# d150_in8.net
KiCad netlist of a schematic drawn in EAGLE
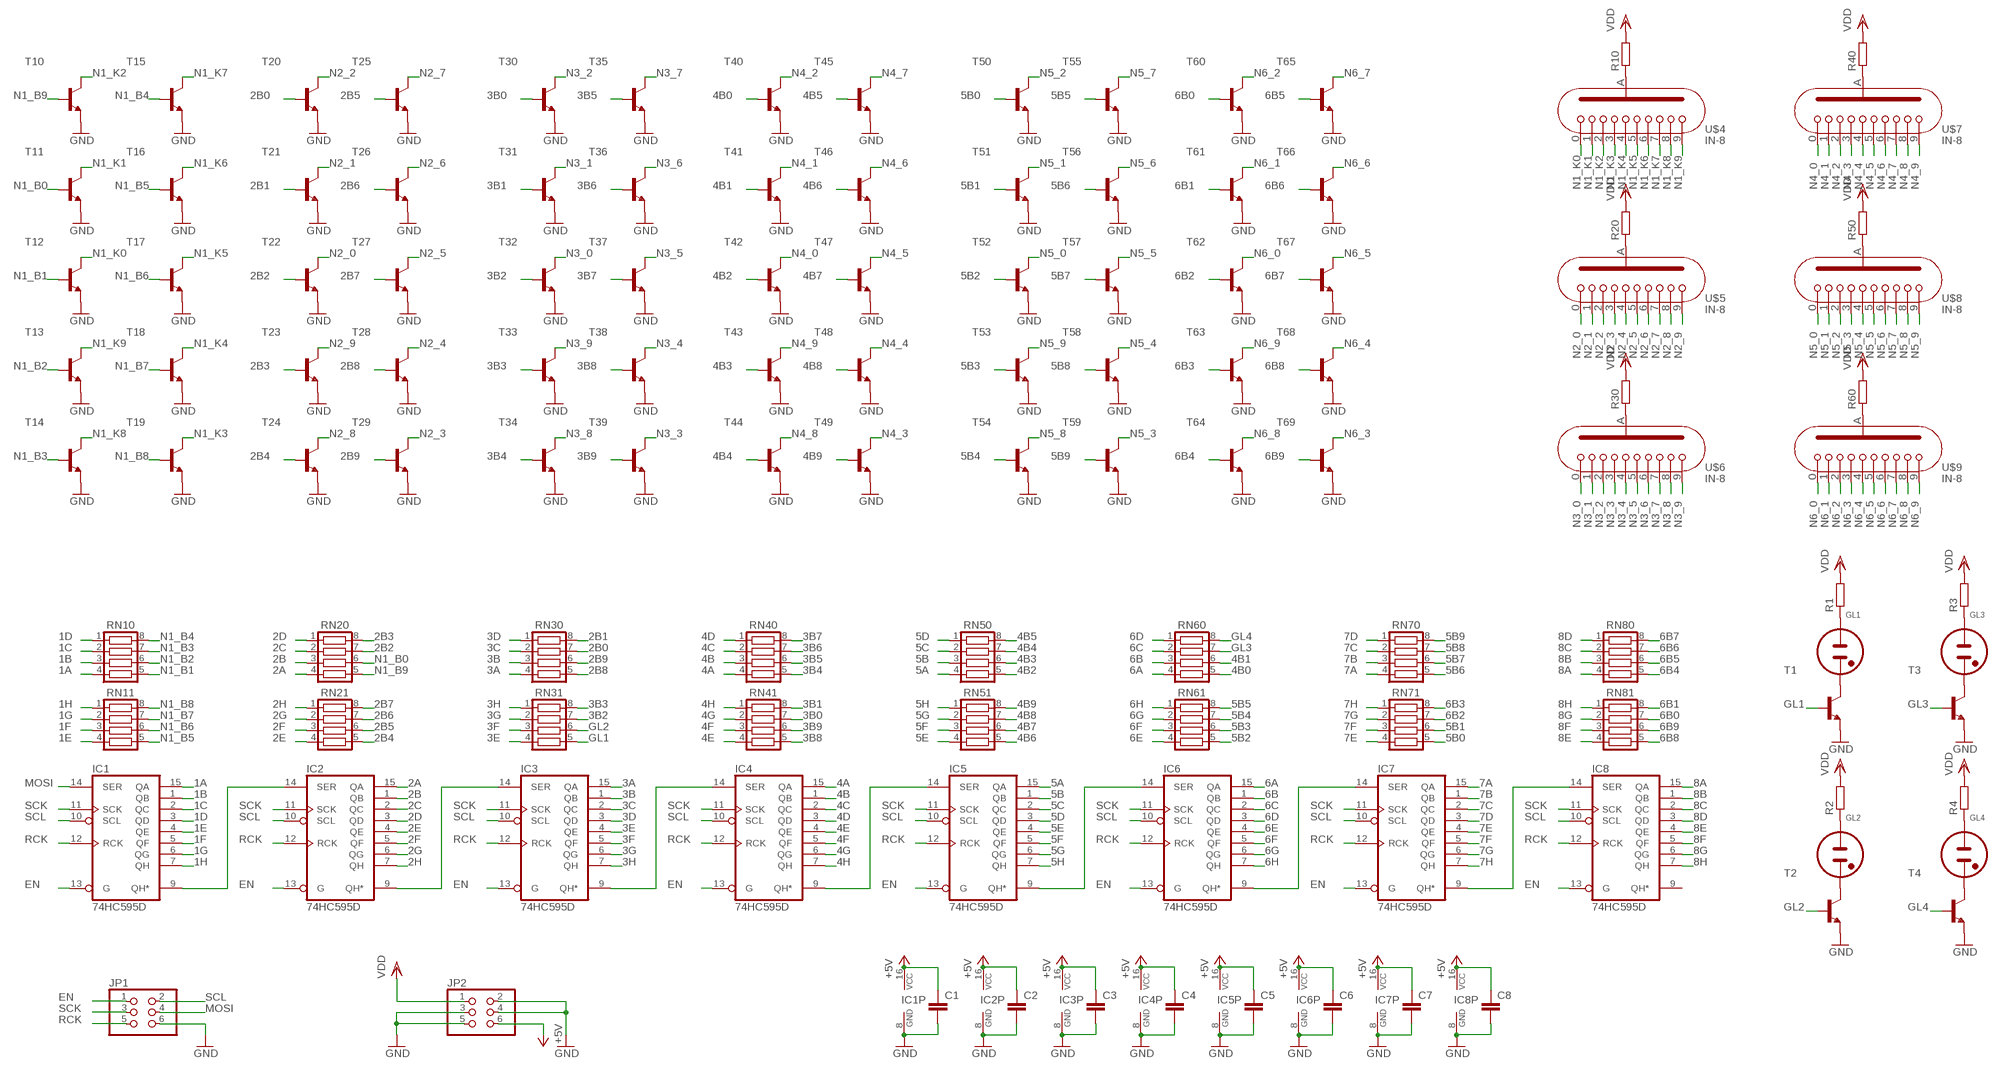
[diagram p0: schematic, sheet 1]

(export (version "E")
  (design (tool "Eeschema 10.0.6"))
  (components
    (comp (ref "C1")
      (value "C-EUC0603")
      (footprint "eagle-import:C0603")
      (libsource (lib "eagle-import") (part "C-EUC0603"))
    )
    (comp (ref "C2")
      (value "C-EUC0603")
      (footprint "eagle-import:C0603")
      (libsource (lib "eagle-import") (part "C-EUC0603"))
    )
    (comp (ref "C3")
      (value "C-EUC0603")
      (footprint "eagle-import:C0603")
      (libsource (lib "eagle-import") (part "C-EUC0603"))
    )
    (comp (ref "C4")
      (value "C-EUC0603")
      (footprint "eagle-import:C0603")
      (libsource (lib "eagle-import") (part "C-EUC0603"))
    )
    (comp (ref "C5")
      (value "C-EUC0603")
      (footprint "eagle-import:C0603")
      (libsource (lib "eagle-import") (part "C-EUC0603"))
    )
    (comp (ref "C6")
      (value "C-EUC0603")
      (footprint "eagle-import:C0603")
      (libsource (lib "eagle-import") (part "C-EUC0603"))
    )
    (comp (ref "C7")
      (value "C-EUC0603")
      (footprint "eagle-import:C0603")
      (libsource (lib "eagle-import") (part "C-EUC0603"))
    )
    (comp (ref "C8")
      (value "C-EUC0603")
      (footprint "eagle-import:C0603")
      (libsource (lib "eagle-import") (part "C-EUC0603"))
    )
    (comp (ref "GL1")
      (value "NE2-NEON-BULB-DRILL")
      (footprint "eagle-import:NE2-NEON-BULB-DRILL")
      (libsource (lib "eagle-import") (part "NE2-NEON-BULB-DRILL"))
    )
    (comp (ref "GL2")
      (value "NE2-NEON-BULB-DRILL")
      (footprint "eagle-import:NE2-NEON-BULB-DRILL")
      (libsource (lib "eagle-import") (part "NE2-NEON-BULB-DRILL"))
    )
    (comp (ref "GL3")
      (value "NE2-NEON-BULB-DRILL")
      (footprint "eagle-import:NE2-NEON-BULB-DRILL")
      (libsource (lib "eagle-import") (part "NE2-NEON-BULB-DRILL"))
    )
    (comp (ref "GL4")
      (value "NE2-NEON-BULB-DRILL")
      (footprint "eagle-import:NE2-NEON-BULB-DRILL")
      (libsource (lib "eagle-import") (part "NE2-NEON-BULB-DRILL"))
    )
    (comp (ref "IC1")
      (value "74HC595D")
      (footprint "eagle-import:SO16")
      (libsource (lib "eagle-import") (part "74595DHC"))
    )
    (comp (ref "IC2")
      (value "74HC595D")
      (footprint "eagle-import:SO16")
      (libsource (lib "eagle-import") (part "74595DHC"))
    )
    (comp (ref "IC3")
      (value "74HC595D")
      (footprint "eagle-import:SO16")
      (libsource (lib "eagle-import") (part "74595DHC"))
    )
    (comp (ref "IC4")
      (value "74HC595D")
      (footprint "eagle-import:SO16")
      (libsource (lib "eagle-import") (part "74595DHC"))
    )
    (comp (ref "IC5")
      (value "74HC595D")
      (footprint "eagle-import:SO16")
      (libsource (lib "eagle-import") (part "74595DHC"))
    )
    (comp (ref "IC6")
      (value "74HC595D")
      (footprint "eagle-import:SO16")
      (libsource (lib "eagle-import") (part "74595DHC"))
    )
    (comp (ref "IC7")
      (value "74HC595D")
      (footprint "eagle-import:SO16")
      (libsource (lib "eagle-import") (part "74595DHC"))
    )
    (comp (ref "IC8")
      (value "74HC595D")
      (footprint "eagle-import:SO16")
      (libsource (lib "eagle-import") (part "74595DHC"))
    )
    (comp (ref "JP1")
      (value "PINHD-2X3_2.54-SMD")
      (footprint "eagle-import:2X03SMD")
      (libsource (lib "eagle-import") (part "PINHD-2X3_2.54-SMD"))
    )
    (comp (ref "JP2")
      (value "PINHD-2X3_2.54-SMD")
      (footprint "eagle-import:2X03SMD")
      (libsource (lib "eagle-import") (part "PINHD-2X3_2.54-SMD"))
    )
    (comp (ref "R1")
      (value "R-EU_R0603")
      (footprint "eagle-import:R0603")
      (libsource (lib "eagle-import") (part "R-EU_R0603"))
    )
    (comp (ref "R2")
      (value "R-EU_R0603")
      (footprint "eagle-import:R0603")
      (libsource (lib "eagle-import") (part "R-EU_R0603"))
    )
    (comp (ref "R3")
      (value "R-EU_R0603")
      (footprint "eagle-import:R0603")
      (libsource (lib "eagle-import") (part "R-EU_R0603"))
    )
    (comp (ref "R4")
      (value "R-EU_R0603")
      (footprint "eagle-import:R0603")
      (libsource (lib "eagle-import") (part "R-EU_R0603"))
    )
    (comp (ref "R10")
      (value "R-EU_R0603")
      (footprint "eagle-import:R0603")
      (libsource (lib "eagle-import") (part "R-EU_R0603"))
    )
    (comp (ref "R20")
      (value "R-EU_R0603")
      (footprint "eagle-import:R0603")
      (libsource (lib "eagle-import") (part "R-EU_R0603"))
    )
    (comp (ref "R30")
      (value "R-EU_R0603")
      (footprint "eagle-import:R0603")
      (libsource (lib "eagle-import") (part "R-EU_R0603"))
    )
    (comp (ref "R40")
      (value "R-EU_R0603")
      (footprint "eagle-import:R0603")
      (libsource (lib "eagle-import") (part "R-EU_R0603"))
    )
    (comp (ref "R50")
      (value "R-EU_R0603")
      (footprint "eagle-import:R0603")
      (libsource (lib "eagle-import") (part "R-EU_R0603"))
    )
    (comp (ref "R60")
      (value "R-EU_R0603")
      (footprint "eagle-import:R0603")
      (libsource (lib "eagle-import") (part "R-EU_R0603"))
    )
    (comp (ref "RN10")
      (value "CTS742C083")
      (footprint "eagle-import:CTS742C083")
      (fields (field (name "OC_FARNELL") "unknown") (field (name "OC_NEWARK") "unknown"))
      (libsource (lib "eagle-import") (part "CTS742C083"))
    )
    (comp (ref "RN11")
      (value "CTS742C083")
      (footprint "eagle-import:CTS742C083")
      (fields (field (name "OC_FARNELL") "unknown") (field (name "OC_NEWARK") "unknown"))
      (libsource (lib "eagle-import") (part "CTS742C083"))
    )
    (comp (ref "RN20")
      (value "CTS742C083")
      (footprint "eagle-import:CTS742C083")
      (fields (field (name "OC_FARNELL") "unknown") (field (name "OC_NEWARK") "unknown"))
      (libsource (lib "eagle-import") (part "CTS742C083"))
    )
    (comp (ref "RN21")
      (value "CTS742C083")
      (footprint "eagle-import:CTS742C083")
      (fields (field (name "OC_FARNELL") "unknown") (field (name "OC_NEWARK") "unknown"))
      (libsource (lib "eagle-import") (part "CTS742C083"))
    )
    (comp (ref "RN30")
      (value "CTS742C083")
      (footprint "eagle-import:CTS742C083")
      (fields (field (name "OC_FARNELL") "unknown") (field (name "OC_NEWARK") "unknown"))
      (libsource (lib "eagle-import") (part "CTS742C083"))
    )
    (comp (ref "RN31")
      (value "CTS742C083")
      (footprint "eagle-import:CTS742C083")
      (fields (field (name "OC_FARNELL") "unknown") (field (name "OC_NEWARK") "unknown"))
      (libsource (lib "eagle-import") (part "CTS742C083"))
    )
    (comp (ref "RN40")
      (value "CTS742C083")
      (footprint "eagle-import:CTS742C083")
      (fields (field (name "OC_FARNELL") "unknown") (field (name "OC_NEWARK") "unknown"))
      (libsource (lib "eagle-import") (part "CTS742C083"))
    )
    (comp (ref "RN41")
      (value "CTS742C083")
      (footprint "eagle-import:CTS742C083")
      (fields (field (name "OC_FARNELL") "unknown") (field (name "OC_NEWARK") "unknown"))
      (libsource (lib "eagle-import") (part "CTS742C083"))
    )
    (comp (ref "RN50")
      (value "CTS742C083")
      (footprint "eagle-import:CTS742C083")
      (fields (field (name "OC_FARNELL") "unknown") (field (name "OC_NEWARK") "unknown"))
      (libsource (lib "eagle-import") (part "CTS742C083"))
    )
    (comp (ref "RN51")
      (value "CTS742C083")
      (footprint "eagle-import:CTS742C083")
      (fields (field (name "OC_FARNELL") "unknown") (field (name "OC_NEWARK") "unknown"))
      (libsource (lib "eagle-import") (part "CTS742C083"))
    )
    (comp (ref "RN60")
      (value "CTS742C083")
      (footprint "eagle-import:CTS742C083")
      (fields (field (name "OC_FARNELL") "unknown") (field (name "OC_NEWARK") "unknown"))
      (libsource (lib "eagle-import") (part "CTS742C083"))
    )
    (comp (ref "RN61")
      (value "CTS742C083")
      (footprint "eagle-import:CTS742C083")
      (fields (field (name "OC_FARNELL") "unknown") (field (name "OC_NEWARK") "unknown"))
      (libsource (lib "eagle-import") (part "CTS742C083"))
    )
    (comp (ref "RN70")
      (value "CTS742C083")
      (footprint "eagle-import:CTS742C083")
      (fields (field (name "OC_FARNELL") "unknown") (field (name "OC_NEWARK") "unknown"))
      (libsource (lib "eagle-import") (part "CTS742C083"))
    )
    (comp (ref "RN71")
      (value "CTS742C083")
      (footprint "eagle-import:CTS742C083")
      (fields (field (name "OC_FARNELL") "unknown") (field (name "OC_NEWARK") "unknown"))
      (libsource (lib "eagle-import") (part "CTS742C083"))
    )
    (comp (ref "RN80")
      (value "CTS742C083")
      (footprint "eagle-import:CTS742C083")
      (fields (field (name "OC_FARNELL") "unknown") (field (name "OC_NEWARK") "unknown"))
      (libsource (lib "eagle-import") (part "CTS742C083"))
    )
    (comp (ref "RN81")
      (value "CTS742C083")
      (footprint "eagle-import:CTS742C083")
      (fields (field (name "OC_FARNELL") "unknown") (field (name "OC_NEWARK") "unknown"))
      (libsource (lib "eagle-import") (part "CTS742C083"))
    )
    (comp (ref "T1")
      (value "SMBTA42")
      (footprint "eagle-import:SOT23")
      (libsource (lib "eagle-import") (part "SMBTA42"))
    )
    (comp (ref "T2")
      (value "SMBTA42")
      (footprint "eagle-import:SOT23")
      (libsource (lib "eagle-import") (part "SMBTA42"))
    )
    (comp (ref "T3")
      (value "SMBTA42")
      (footprint "eagle-import:SOT23")
      (libsource (lib "eagle-import") (part "SMBTA42"))
    )
    (comp (ref "T4")
      (value "SMBTA42")
      (footprint "eagle-import:SOT23")
      (libsource (lib "eagle-import") (part "SMBTA42"))
    )
    (comp (ref "T10")
      (value "SMBTA42")
      (footprint "eagle-import:SOT23")
      (libsource (lib "eagle-import") (part "SMBTA42"))
    )
    (comp (ref "T11")
      (value "SMBTA42")
      (footprint "eagle-import:SOT23")
      (libsource (lib "eagle-import") (part "SMBTA42"))
    )
    (comp (ref "T12")
      (value "SMBTA42")
      (footprint "eagle-import:SOT23")
      (libsource (lib "eagle-import") (part "SMBTA42"))
    )
    (comp (ref "T13")
      (value "SMBTA42")
      (footprint "eagle-import:SOT23")
      (libsource (lib "eagle-import") (part "SMBTA42"))
    )
    (comp (ref "T14")
      (value "SMBTA42")
      (footprint "eagle-import:SOT23")
      (libsource (lib "eagle-import") (part "SMBTA42"))
    )
    (comp (ref "T15")
      (value "SMBTA42")
      (footprint "eagle-import:SOT23")
      (libsource (lib "eagle-import") (part "SMBTA42"))
    )
    (comp (ref "T16")
      (value "SMBTA42")
      (footprint "eagle-import:SOT23")
      (libsource (lib "eagle-import") (part "SMBTA42"))
    )
    (comp (ref "T17")
      (value "SMBTA42")
      (footprint "eagle-import:SOT23")
      (libsource (lib "eagle-import") (part "SMBTA42"))
    )
    (comp (ref "T18")
      (value "SMBTA42")
      (footprint "eagle-import:SOT23")
      (libsource (lib "eagle-import") (part "SMBTA42"))
    )
    (comp (ref "T19")
      (value "SMBTA42")
      (footprint "eagle-import:SOT23")
      (libsource (lib "eagle-import") (part "SMBTA42"))
    )
    (comp (ref "T20")
      (value "SMBTA42")
      (footprint "eagle-import:SOT23")
      (libsource (lib "eagle-import") (part "SMBTA42"))
    )
    (comp (ref "T21")
      (value "SMBTA42")
      (footprint "eagle-import:SOT23")
      (libsource (lib "eagle-import") (part "SMBTA42"))
    )
    (comp (ref "T22")
      (value "SMBTA42")
      (footprint "eagle-import:SOT23")
      (libsource (lib "eagle-import") (part "SMBTA42"))
    )
    (comp (ref "T23")
      (value "SMBTA42")
      (footprint "eagle-import:SOT23")
      (libsource (lib "eagle-import") (part "SMBTA42"))
    )
    (comp (ref "T24")
      (value "SMBTA42")
      (footprint "eagle-import:SOT23")
      (libsource (lib "eagle-import") (part "SMBTA42"))
    )
    (comp (ref "T25")
      (value "SMBTA42")
      (footprint "eagle-import:SOT23")
      (libsource (lib "eagle-import") (part "SMBTA42"))
    )
    (comp (ref "T26")
      (value "SMBTA42")
      (footprint "eagle-import:SOT23")
      (libsource (lib "eagle-import") (part "SMBTA42"))
    )
    (comp (ref "T27")
      (value "SMBTA42")
      (footprint "eagle-import:SOT23")
      (libsource (lib "eagle-import") (part "SMBTA42"))
    )
    (comp (ref "T28")
      (value "SMBTA42")
      (footprint "eagle-import:SOT23")
      (libsource (lib "eagle-import") (part "SMBTA42"))
    )
    (comp (ref "T29")
      (value "SMBTA42")
      (footprint "eagle-import:SOT23")
      (libsource (lib "eagle-import") (part "SMBTA42"))
    )
    (comp (ref "T30")
      (value "SMBTA42")
      (footprint "eagle-import:SOT23")
      (libsource (lib "eagle-import") (part "SMBTA42"))
    )
    (comp (ref "T31")
      (value "SMBTA42")
      (footprint "eagle-import:SOT23")
      (libsource (lib "eagle-import") (part "SMBTA42"))
    )
    (comp (ref "T32")
      (value "SMBTA42")
      (footprint "eagle-import:SOT23")
      (libsource (lib "eagle-import") (part "SMBTA42"))
    )
    (comp (ref "T33")
      (value "SMBTA42")
      (footprint "eagle-import:SOT23")
      (libsource (lib "eagle-import") (part "SMBTA42"))
    )
    (comp (ref "T34")
      (value "SMBTA42")
      (footprint "eagle-import:SOT23")
      (libsource (lib "eagle-import") (part "SMBTA42"))
    )
    (comp (ref "T35")
      (value "SMBTA42")
      (footprint "eagle-import:SOT23")
      (libsource (lib "eagle-import") (part "SMBTA42"))
    )
    (comp (ref "T36")
      (value "SMBTA42")
      (footprint "eagle-import:SOT23")
      (libsource (lib "eagle-import") (part "SMBTA42"))
    )
    (comp (ref "T37")
      (value "SMBTA42")
      (footprint "eagle-import:SOT23")
      (libsource (lib "eagle-import") (part "SMBTA42"))
    )
    (comp (ref "T38")
      (value "SMBTA42")
      (footprint "eagle-import:SOT23")
      (libsource (lib "eagle-import") (part "SMBTA42"))
    )
    (comp (ref "T39")
      (value "SMBTA42")
      (footprint "eagle-import:SOT23")
      (libsource (lib "eagle-import") (part "SMBTA42"))
    )
    (comp (ref "T40")
      (value "SMBTA42")
      (footprint "eagle-import:SOT23")
      (libsource (lib "eagle-import") (part "SMBTA42"))
    )
    (comp (ref "T41")
      (value "SMBTA42")
      (footprint "eagle-import:SOT23")
      (libsource (lib "eagle-import") (part "SMBTA42"))
    )
    (comp (ref "T42")
      (value "SMBTA42")
      (footprint "eagle-import:SOT23")
      (libsource (lib "eagle-import") (part "SMBTA42"))
    )
    (comp (ref "T43")
      (value "SMBTA42")
      (footprint "eagle-import:SOT23")
      (libsource (lib "eagle-import") (part "SMBTA42"))
    )
    (comp (ref "T44")
      (value "SMBTA42")
      (footprint "eagle-import:SOT23")
      (libsource (lib "eagle-import") (part "SMBTA42"))
    )
    (comp (ref "T45")
      (value "SMBTA42")
      (footprint "eagle-import:SOT23")
      (libsource (lib "eagle-import") (part "SMBTA42"))
    )
    (comp (ref "T46")
      (value "SMBTA42")
      (footprint "eagle-import:SOT23")
      (libsource (lib "eagle-import") (part "SMBTA42"))
    )
    (comp (ref "T47")
      (value "SMBTA42")
      (footprint "eagle-import:SOT23")
      (libsource (lib "eagle-import") (part "SMBTA42"))
    )
    (comp (ref "T48")
      (value "SMBTA42")
      (footprint "eagle-import:SOT23")
      (libsource (lib "eagle-import") (part "SMBTA42"))
    )
    (comp (ref "T49")
      (value "SMBTA42")
      (footprint "eagle-import:SOT23")
      (libsource (lib "eagle-import") (part "SMBTA42"))
    )
    (comp (ref "T50")
      (value "SMBTA42")
      (footprint "eagle-import:SOT23")
      (libsource (lib "eagle-import") (part "SMBTA42"))
    )
    (comp (ref "T51")
      (value "SMBTA42")
      (footprint "eagle-import:SOT23")
      (libsource (lib "eagle-import") (part "SMBTA42"))
    )
    (comp (ref "T52")
      (value "SMBTA42")
      (footprint "eagle-import:SOT23")
      (libsource (lib "eagle-import") (part "SMBTA42"))
    )
    (comp (ref "T53")
      (value "SMBTA42")
      (footprint "eagle-import:SOT23")
      (libsource (lib "eagle-import") (part "SMBTA42"))
    )
    (comp (ref "T54")
      (value "SMBTA42")
      (footprint "eagle-import:SOT23")
      (libsource (lib "eagle-import") (part "SMBTA42"))
    )
    (comp (ref "T55")
      (value "SMBTA42")
      (footprint "eagle-import:SOT23")
      (libsource (lib "eagle-import") (part "SMBTA42"))
    )
    (comp (ref "T56")
      (value "SMBTA42")
      (footprint "eagle-import:SOT23")
      (libsource (lib "eagle-import") (part "SMBTA42"))
    )
    (comp (ref "T57")
      (value "SMBTA42")
      (footprint "eagle-import:SOT23")
      (libsource (lib "eagle-import") (part "SMBTA42"))
    )
    (comp (ref "T58")
      (value "SMBTA42")
      (footprint "eagle-import:SOT23")
      (libsource (lib "eagle-import") (part "SMBTA42"))
    )
    (comp (ref "T59")
      (value "SMBTA42")
      (footprint "eagle-import:SOT23")
      (libsource (lib "eagle-import") (part "SMBTA42"))
    )
    (comp (ref "T60")
      (value "SMBTA42")
      (footprint "eagle-import:SOT23")
      (libsource (lib "eagle-import") (part "SMBTA42"))
    )
    (comp (ref "T61")
      (value "SMBTA42")
      (footprint "eagle-import:SOT23")
      (libsource (lib "eagle-import") (part "SMBTA42"))
    )
    (comp (ref "T62")
      (value "SMBTA42")
      (footprint "eagle-import:SOT23")
      (libsource (lib "eagle-import") (part "SMBTA42"))
    )
    (comp (ref "T63")
      (value "SMBTA42")
      (footprint "eagle-import:SOT23")
      (libsource (lib "eagle-import") (part "SMBTA42"))
    )
    (comp (ref "T64")
      (value "SMBTA42")
      (footprint "eagle-import:SOT23")
      (libsource (lib "eagle-import") (part "SMBTA42"))
    )
    (comp (ref "T65")
      (value "SMBTA42")
      (footprint "eagle-import:SOT23")
      (libsource (lib "eagle-import") (part "SMBTA42"))
    )
    (comp (ref "T66")
      (value "SMBTA42")
      (footprint "eagle-import:SOT23")
      (libsource (lib "eagle-import") (part "SMBTA42"))
    )
    (comp (ref "T67")
      (value "SMBTA42")
      (footprint "eagle-import:SOT23")
      (libsource (lib "eagle-import") (part "SMBTA42"))
    )
    (comp (ref "T68")
      (value "SMBTA42")
      (footprint "eagle-import:SOT23")
      (libsource (lib "eagle-import") (part "SMBTA42"))
    )
    (comp (ref "T69")
      (value "SMBTA42")
      (footprint "eagle-import:SOT23")
      (libsource (lib "eagle-import") (part "SMBTA42"))
    )
    (comp (ref "U$4")
      (value "IN-8")
      (footprint "eagle-import:IN-8")
      (libsource (lib "eagle-import") (part "IN-8"))
    )
    (comp (ref "U$5")
      (value "IN-8")
      (footprint "eagle-import:IN-8")
      (libsource (lib "eagle-import") (part "IN-8"))
    )
    (comp (ref "U$6")
      (value "IN-8")
      (footprint "eagle-import:IN-8")
      (libsource (lib "eagle-import") (part "IN-8"))
    )
    (comp (ref "U$7")
      (value "IN-8")
      (footprint "eagle-import:IN-8")
      (libsource (lib "eagle-import") (part "IN-8"))
    )
    (comp (ref "U$8")
      (value "IN-8")
      (footprint "eagle-import:IN-8")
      (libsource (lib "eagle-import") (part "IN-8"))
    )
    (comp (ref "U$9")
      (value "IN-8")
      (footprint "eagle-import:IN-8")
      (libsource (lib "eagle-import") (part "IN-8"))
    )
  )
  (nets
    (net (code "1") (name "+5V") (class "Default")
      (node (ref "C1") (pin "1") (pinfunction "1_1") (pintype "passive"))
      (node (ref "C2") (pin "1") (pinfunction "1_1") (pintype "passive"))
      (node (ref "C3") (pin "1") (pinfunction "1_1") (pintype "passive"))
      (node (ref "C4") (pin "1") (pinfunction "1_1") (pintype "passive"))
      (node (ref "C5") (pin "1") (pinfunction "1_1") (pintype "passive"))
      (node (ref "C6") (pin "1") (pinfunction "1_1") (pintype "passive"))
      (node (ref "C7") (pin "1") (pinfunction "1_1") (pintype "passive"))
      (node (ref "C8") (pin "1") (pinfunction "1_1") (pintype "passive"))
      (node (ref "IC1") (pin "16") (pinfunction "VCC_16") (pintype "power_in"))
      (node (ref "IC2") (pin "16") (pinfunction "VCC_16") (pintype "power_in"))
      (node (ref "IC3") (pin "16") (pinfunction "VCC_16") (pintype "power_in"))
      (node (ref "IC4") (pin "16") (pinfunction "VCC_16") (pintype "power_in"))
      (node (ref "IC5") (pin "16") (pinfunction "VCC_16") (pintype "power_in"))
      (node (ref "IC6") (pin "16") (pinfunction "VCC_16") (pintype "power_in"))
      (node (ref "IC7") (pin "16") (pinfunction "VCC_16") (pintype "power_in"))
      (node (ref "IC8") (pin "16") (pinfunction "VCC_16") (pintype "power_in"))
      (node (ref "JP2") (pin "6") (pinfunction "6_6") (pintype "passive"))
    )
    (net (code "2") (name "/1A") (class "Default")
      (node (ref "IC1") (pin "15") (pinfunction "QA_15") (pintype "tri_state"))
      (node (ref "RN10") (pin "4") (pinfunction "4_4") (pintype "passive"))
    )
    (net (code "3") (name "/1B") (class "Default")
      (node (ref "IC1") (pin "1") (pinfunction "QB_1") (pintype "tri_state"))
      (node (ref "RN10") (pin "3") (pinfunction "3_3") (pintype "passive"))
    )
    (net (code "4") (name "/1C") (class "Default")
      (node (ref "IC1") (pin "2") (pinfunction "QC_2") (pintype "tri_state"))
      (node (ref "RN10") (pin "2") (pinfunction "2_2") (pintype "passive"))
    )
    (net (code "5") (name "/1D") (class "Default")
      (node (ref "IC1") (pin "3") (pinfunction "QD_3") (pintype "tri_state"))
      (node (ref "RN10") (pin "1") (pinfunction "1_1") (pintype "passive"))
    )
    (net (code "6") (name "/1E") (class "Default")
      (node (ref "IC1") (pin "4") (pinfunction "QE_4") (pintype "tri_state"))
      (node (ref "RN11") (pin "4") (pinfunction "4_4") (pintype "passive"))
    )
    (net (code "7") (name "/1F") (class "Default")
      (node (ref "IC1") (pin "5") (pinfunction "QF_5") (pintype "tri_state"))
      (node (ref "RN11") (pin "3") (pinfunction "3_3") (pintype "passive"))
    )
    (net (code "8") (name "/1G") (class "Default")
      (node (ref "IC1") (pin "6") (pinfunction "QG_6") (pintype "tri_state"))
      (node (ref "RN11") (pin "2") (pinfunction "2_2") (pintype "passive"))
    )
    (net (code "9") (name "/1H") (class "Default")
      (node (ref "IC1") (pin "7") (pinfunction "QH_7") (pintype "tri_state"))
      (node (ref "RN11") (pin "1") (pinfunction "1_1") (pintype "passive"))
    )
    (net (code "10") (name "/2A") (class "Default")
      (node (ref "IC2") (pin "15") (pinfunction "QA_15") (pintype "tri_state"))
      (node (ref "RN20") (pin "4") (pinfunction "4_4") (pintype "passive"))
    )
    (net (code "11") (name "/2B") (class "Default")
      (node (ref "IC2") (pin "1") (pinfunction "QB_1") (pintype "tri_state"))
      (node (ref "RN20") (pin "3") (pinfunction "3_3") (pintype "passive"))
    )
    (net (code "12") (name "/2B0") (class "Default")
      (node (ref "RN30") (pin "7") (pinfunction "7_7") (pintype "passive"))
      (node (ref "T20") (pin "1") (pinfunction "B_1") (pintype "passive"))
    )
    (net (code "13") (name "/2B1") (class "Default")
      (node (ref "RN30") (pin "8") (pinfunction "8_8") (pintype "passive"))
      (node (ref "T21") (pin "1") (pinfunction "B_1") (pintype "passive"))
    )
    (net (code "14") (name "/2B2") (class "Default")
      (node (ref "RN20") (pin "7") (pinfunction "7_7") (pintype "passive"))
      (node (ref "T22") (pin "1") (pinfunction "B_1") (pintype "passive"))
    )
    (net (code "15") (name "/2B3") (class "Default")
      (node (ref "RN20") (pin "8") (pinfunction "8_8") (pintype "passive"))
      (node (ref "T23") (pin "1") (pinfunction "B_1") (pintype "passive"))
    )
    (net (code "16") (name "/2B4") (class "Default")
      (node (ref "RN21") (pin "5") (pinfunction "5_5") (pintype "passive"))
      (node (ref "T24") (pin "1") (pinfunction "B_1") (pintype "passive"))
    )
    (net (code "17") (name "/2B5") (class "Default")
      (node (ref "RN21") (pin "6") (pinfunction "6_6") (pintype "passive"))
      (node (ref "T25") (pin "1") (pinfunction "B_1") (pintype "passive"))
    )
    (net (code "18") (name "/2B6") (class "Default")
      (node (ref "RN21") (pin "7") (pinfunction "7_7") (pintype "passive"))
      (node (ref "T26") (pin "1") (pinfunction "B_1") (pintype "passive"))
    )
    (net (code "19") (name "/2B7") (class "Default")
      (node (ref "RN21") (pin "8") (pinfunction "8_8") (pintype "passive"))
      (node (ref "T27") (pin "1") (pinfunction "B_1") (pintype "passive"))
    )
    (net (code "20") (name "/2B8") (class "Default")
      (node (ref "RN30") (pin "5") (pinfunction "5_5") (pintype "passive"))
      (node (ref "T28") (pin "1") (pinfunction "B_1") (pintype "passive"))
    )
    (net (code "21") (name "/2B9") (class "Default")
      (node (ref "RN30") (pin "6") (pinfunction "6_6") (pintype "passive"))
      (node (ref "T29") (pin "1") (pinfunction "B_1") (pintype "passive"))
    )
    (net (code "22") (name "/2C") (class "Default")
      (node (ref "IC2") (pin "2") (pinfunction "QC_2") (pintype "tri_state"))
      (node (ref "RN20") (pin "2") (pinfunction "2_2") (pintype "passive"))
    )
    (net (code "23") (name "/2D") (class "Default")
      (node (ref "IC2") (pin "3") (pinfunction "QD_3") (pintype "tri_state"))
      (node (ref "RN20") (pin "1") (pinfunction "1_1") (pintype "passive"))
    )
    (net (code "24") (name "/2E") (class "Default")
      (node (ref "IC2") (pin "4") (pinfunction "QE_4") (pintype "tri_state"))
      (node (ref "RN21") (pin "4") (pinfunction "4_4") (pintype "passive"))
    )
    (net (code "25") (name "/2F") (class "Default")
      (node (ref "IC2") (pin "5") (pinfunction "QF_5") (pintype "tri_state"))
      (node (ref "RN21") (pin "3") (pinfunction "3_3") (pintype "passive"))
    )
    (net (code "26") (name "/2G") (class "Default")
      (node (ref "IC2") (pin "6") (pinfunction "QG_6") (pintype "tri_state"))
      (node (ref "RN21") (pin "2") (pinfunction "2_2") (pintype "passive"))
    )
    (net (code "27") (name "/2H") (class "Default")
      (node (ref "IC2") (pin "7") (pinfunction "QH_7") (pintype "tri_state"))
      (node (ref "RN21") (pin "1") (pinfunction "1_1") (pintype "passive"))
    )
    (net (code "28") (name "/3A") (class "Default")
      (node (ref "IC3") (pin "15") (pinfunction "QA_15") (pintype "tri_state"))
      (node (ref "RN30") (pin "4") (pinfunction "4_4") (pintype "passive"))
    )
    (net (code "29") (name "/3B") (class "Default")
      (node (ref "IC3") (pin "1") (pinfunction "QB_1") (pintype "tri_state"))
      (node (ref "RN30") (pin "3") (pinfunction "3_3") (pintype "passive"))
    )
    (net (code "30") (name "/3B0") (class "Default")
      (node (ref "RN41") (pin "7") (pinfunction "7_7") (pintype "passive"))
      (node (ref "T30") (pin "1") (pinfunction "B_1") (pintype "passive"))
    )
    (net (code "31") (name "/3B1") (class "Default")
      (node (ref "RN41") (pin "8") (pinfunction "8_8") (pintype "passive"))
      (node (ref "T31") (pin "1") (pinfunction "B_1") (pintype "passive"))
    )
    (net (code "32") (name "/3B2") (class "Default")
      (node (ref "RN31") (pin "7") (pinfunction "7_7") (pintype "passive"))
      (node (ref "T32") (pin "1") (pinfunction "B_1") (pintype "passive"))
    )
    (net (code "33") (name "/3B3") (class "Default")
      (node (ref "RN31") (pin "8") (pinfunction "8_8") (pintype "passive"))
      (node (ref "T33") (pin "1") (pinfunction "B_1") (pintype "passive"))
    )
    (net (code "34") (name "/3B4") (class "Default")
      (node (ref "RN40") (pin "5") (pinfunction "5_5") (pintype "passive"))
      (node (ref "T34") (pin "1") (pinfunction "B_1") (pintype "passive"))
    )
    (net (code "35") (name "/3B5") (class "Default")
      (node (ref "RN40") (pin "6") (pinfunction "6_6") (pintype "passive"))
      (node (ref "T35") (pin "1") (pinfunction "B_1") (pintype "passive"))
    )
    (net (code "36") (name "/3B6") (class "Default")
      (node (ref "RN40") (pin "7") (pinfunction "7_7") (pintype "passive"))
      (node (ref "T36") (pin "1") (pinfunction "B_1") (pintype "passive"))
    )
    (net (code "37") (name "/3B7") (class "Default")
      (node (ref "RN40") (pin "8") (pinfunction "8_8") (pintype "passive"))
      (node (ref "T37") (pin "1") (pinfunction "B_1") (pintype "passive"))
    )
    (net (code "38") (name "/3B8") (class "Default")
      (node (ref "RN41") (pin "5") (pinfunction "5_5") (pintype "passive"))
      (node (ref "T38") (pin "1") (pinfunction "B_1") (pintype "passive"))
    )
    (net (code "39") (name "/3B9") (class "Default")
      (node (ref "RN41") (pin "6") (pinfunction "6_6") (pintype "passive"))
      (node (ref "T39") (pin "1") (pinfunction "B_1") (pintype "passive"))
    )
    (net (code "40") (name "/3C") (class "Default")
      (node (ref "IC3") (pin "2") (pinfunction "QC_2") (pintype "tri_state"))
      (node (ref "RN30") (pin "2") (pinfunction "2_2") (pintype "passive"))
    )
    (net (code "41") (name "/3D") (class "Default")
      (node (ref "IC3") (pin "3") (pinfunction "QD_3") (pintype "tri_state"))
      (node (ref "RN30") (pin "1") (pinfunction "1_1") (pintype "passive"))
    )
    (net (code "42") (name "/3E") (class "Default")
      (node (ref "IC3") (pin "4") (pinfunction "QE_4") (pintype "tri_state"))
      (node (ref "RN31") (pin "4") (pinfunction "4_4") (pintype "passive"))
    )
    (net (code "43") (name "/3F") (class "Default")
      (node (ref "IC3") (pin "5") (pinfunction "QF_5") (pintype "tri_state"))
      (node (ref "RN31") (pin "3") (pinfunction "3_3") (pintype "passive"))
    )
    (net (code "44") (name "/3G") (class "Default")
      (node (ref "IC3") (pin "6") (pinfunction "QG_6") (pintype "tri_state"))
      (node (ref "RN31") (pin "2") (pinfunction "2_2") (pintype "passive"))
    )
    (net (code "45") (name "/3H") (class "Default")
      (node (ref "IC3") (pin "7") (pinfunction "QH_7") (pintype "tri_state"))
      (node (ref "RN31") (pin "1") (pinfunction "1_1") (pintype "passive"))
    )
    (net (code "46") (name "/4A") (class "Default")
      (node (ref "IC4") (pin "15") (pinfunction "QA_15") (pintype "tri_state"))
      (node (ref "RN40") (pin "4") (pinfunction "4_4") (pintype "passive"))
    )
    (net (code "47") (name "/4B") (class "Default")
      (node (ref "IC4") (pin "1") (pinfunction "QB_1") (pintype "tri_state"))
      (node (ref "RN40") (pin "3") (pinfunction "3_3") (pintype "passive"))
    )
    (net (code "48") (name "/4B0") (class "Default")
      (node (ref "RN60") (pin "5") (pinfunction "5_5") (pintype "passive"))
      (node (ref "T40") (pin "1") (pinfunction "B_1") (pintype "passive"))
    )
    (net (code "49") (name "/4B1") (class "Default")
      (node (ref "RN60") (pin "6") (pinfunction "6_6") (pintype "passive"))
      (node (ref "T41") (pin "1") (pinfunction "B_1") (pintype "passive"))
    )
    (net (code "50") (name "/4B2") (class "Default")
      (node (ref "RN50") (pin "5") (pinfunction "5_5") (pintype "passive"))
      (node (ref "T42") (pin "1") (pinfunction "B_1") (pintype "passive"))
    )
    (net (code "51") (name "/4B3") (class "Default")
      (node (ref "RN50") (pin "6") (pinfunction "6_6") (pintype "passive"))
      (node (ref "T43") (pin "1") (pinfunction "B_1") (pintype "passive"))
    )
    (net (code "52") (name "/4B4") (class "Default")
      (node (ref "RN50") (pin "7") (pinfunction "7_7") (pintype "passive"))
      (node (ref "T44") (pin "1") (pinfunction "B_1") (pintype "passive"))
    )
    (net (code "53") (name "/4B5") (class "Default")
      (node (ref "RN50") (pin "8") (pinfunction "8_8") (pintype "passive"))
      (node (ref "T45") (pin "1") (pinfunction "B_1") (pintype "passive"))
    )
    (net (code "54") (name "/4B6") (class "Default")
      (node (ref "RN51") (pin "5") (pinfunction "5_5") (pintype "passive"))
      (node (ref "T46") (pin "1") (pinfunction "B_1") (pintype "passive"))
    )
    (net (code "55") (name "/4B7") (class "Default")
      (node (ref "RN51") (pin "6") (pinfunction "6_6") (pintype "passive"))
      (node (ref "T47") (pin "1") (pinfunction "B_1") (pintype "passive"))
    )
    (net (code "56") (name "/4B8") (class "Default")
      (node (ref "RN51") (pin "7") (pinfunction "7_7") (pintype "passive"))
      (node (ref "T48") (pin "1") (pinfunction "B_1") (pintype "passive"))
    )
    (net (code "57") (name "/4B9") (class "Default")
      (node (ref "RN51") (pin "8") (pinfunction "8_8") (pintype "passive"))
      (node (ref "T49") (pin "1") (pinfunction "B_1") (pintype "passive"))
    )
    (net (code "58") (name "/4C") (class "Default")
      (node (ref "IC4") (pin "2") (pinfunction "QC_2") (pintype "tri_state"))
      (node (ref "RN40") (pin "2") (pinfunction "2_2") (pintype "passive"))
    )
    (net (code "59") (name "/4D") (class "Default")
      (node (ref "IC4") (pin "3") (pinfunction "QD_3") (pintype "tri_state"))
      (node (ref "RN40") (pin "1") (pinfunction "1_1") (pintype "passive"))
    )
    (net (code "60") (name "/4E") (class "Default")
      (node (ref "IC4") (pin "4") (pinfunction "QE_4") (pintype "tri_state"))
      (node (ref "RN41") (pin "4") (pinfunction "4_4") (pintype "passive"))
    )
    (net (code "61") (name "/4F") (class "Default")
      (node (ref "IC4") (pin "5") (pinfunction "QF_5") (pintype "tri_state"))
      (node (ref "RN41") (pin "3") (pinfunction "3_3") (pintype "passive"))
    )
    (net (code "62") (name "/4G") (class "Default")
      (node (ref "IC4") (pin "6") (pinfunction "QG_6") (pintype "tri_state"))
      (node (ref "RN41") (pin "2") (pinfunction "2_2") (pintype "passive"))
    )
    (net (code "63") (name "/4H") (class "Default")
      (node (ref "IC4") (pin "7") (pinfunction "QH_7") (pintype "tri_state"))
      (node (ref "RN41") (pin "1") (pinfunction "1_1") (pintype "passive"))
    )
    (net (code "64") (name "/5A") (class "Default")
      (node (ref "IC5") (pin "15") (pinfunction "QA_15") (pintype "tri_state"))
      (node (ref "RN50") (pin "4") (pinfunction "4_4") (pintype "passive"))
    )
    (net (code "65") (name "/5B") (class "Default")
      (node (ref "IC5") (pin "1") (pinfunction "QB_1") (pintype "tri_state"))
      (node (ref "RN50") (pin "3") (pinfunction "3_3") (pintype "passive"))
    )
    (net (code "66") (name "/5B0") (class "Default")
      (node (ref "RN71") (pin "5") (pinfunction "5_5") (pintype "passive"))
      (node (ref "T50") (pin "1") (pinfunction "B_1") (pintype "passive"))
    )
    (net (code "67") (name "/5B1") (class "Default")
      (node (ref "RN71") (pin "6") (pinfunction "6_6") (pintype "passive"))
      (node (ref "T51") (pin "1") (pinfunction "B_1") (pintype "passive"))
    )
    (net (code "68") (name "/5B2") (class "Default")
      (node (ref "RN61") (pin "5") (pinfunction "5_5") (pintype "passive"))
      (node (ref "T52") (pin "1") (pinfunction "B_1") (pintype "passive"))
    )
    (net (code "69") (name "/5B3") (class "Default")
      (node (ref "RN61") (pin "6") (pinfunction "6_6") (pintype "passive"))
      (node (ref "T53") (pin "1") (pinfunction "B_1") (pintype "passive"))
    )
    (net (code "70") (name "/5B4") (class "Default")
      (node (ref "RN61") (pin "7") (pinfunction "7_7") (pintype "passive"))
      (node (ref "T54") (pin "1") (pinfunction "B_1") (pintype "passive"))
    )
    (net (code "71") (name "/5B5") (class "Default")
      (node (ref "RN61") (pin "8") (pinfunction "8_8") (pintype "passive"))
      (node (ref "T55") (pin "1") (pinfunction "B_1") (pintype "passive"))
    )
    (net (code "72") (name "/5B6") (class "Default")
      (node (ref "RN70") (pin "5") (pinfunction "5_5") (pintype "passive"))
      (node (ref "T56") (pin "1") (pinfunction "B_1") (pintype "passive"))
    )
    (net (code "73") (name "/5B7") (class "Default")
      (node (ref "RN70") (pin "6") (pinfunction "6_6") (pintype "passive"))
      (node (ref "T57") (pin "1") (pinfunction "B_1") (pintype "passive"))
    )
    (net (code "74") (name "/5B8") (class "Default")
      (node (ref "RN70") (pin "7") (pinfunction "7_7") (pintype "passive"))
      (node (ref "T58") (pin "1") (pinfunction "B_1") (pintype "passive"))
    )
    (net (code "75") (name "/5B9") (class "Default")
      (node (ref "RN70") (pin "8") (pinfunction "8_8") (pintype "passive"))
      (node (ref "T59") (pin "1") (pinfunction "B_1") (pintype "passive"))
    )
    (net (code "76") (name "/5C") (class "Default")
      (node (ref "IC5") (pin "2") (pinfunction "QC_2") (pintype "tri_state"))
      (node (ref "RN50") (pin "2") (pinfunction "2_2") (pintype "passive"))
    )
    (net (code "77") (name "/5D") (class "Default")
      (node (ref "IC5") (pin "3") (pinfunction "QD_3") (pintype "tri_state"))
      (node (ref "RN50") (pin "1") (pinfunction "1_1") (pintype "passive"))
    )
    (net (code "78") (name "/5E") (class "Default")
      (node (ref "IC5") (pin "4") (pinfunction "QE_4") (pintype "tri_state"))
      (node (ref "RN51") (pin "4") (pinfunction "4_4") (pintype "passive"))
    )
    (net (code "79") (name "/5F") (class "Default")
      (node (ref "IC5") (pin "5") (pinfunction "QF_5") (pintype "tri_state"))
      (node (ref "RN51") (pin "3") (pinfunction "3_3") (pintype "passive"))
    )
    (net (code "80") (name "/5G") (class "Default")
      (node (ref "IC5") (pin "6") (pinfunction "QG_6") (pintype "tri_state"))
      (node (ref "RN51") (pin "2") (pinfunction "2_2") (pintype "passive"))
    )
    (net (code "81") (name "/5H") (class "Default")
      (node (ref "IC5") (pin "7") (pinfunction "QH_7") (pintype "tri_state"))
      (node (ref "RN51") (pin "1") (pinfunction "1_1") (pintype "passive"))
    )
    (net (code "82") (name "/6A") (class "Default")
      (node (ref "IC6") (pin "15") (pinfunction "QA_15") (pintype "tri_state"))
      (node (ref "RN60") (pin "4") (pinfunction "4_4") (pintype "passive"))
    )
    (net (code "83") (name "/6B") (class "Default")
      (node (ref "IC6") (pin "1") (pinfunction "QB_1") (pintype "tri_state"))
      (node (ref "RN60") (pin "3") (pinfunction "3_3") (pintype "passive"))
    )
    (net (code "84") (name "/6B0") (class "Default")
      (node (ref "RN81") (pin "7") (pinfunction "7_7") (pintype "passive"))
      (node (ref "T60") (pin "1") (pinfunction "B_1") (pintype "passive"))
    )
    (net (code "85") (name "/6B1") (class "Default")
      (node (ref "RN81") (pin "8") (pinfunction "8_8") (pintype "passive"))
      (node (ref "T61") (pin "1") (pinfunction "B_1") (pintype "passive"))
    )
    (net (code "86") (name "/6B2") (class "Default")
      (node (ref "RN71") (pin "7") (pinfunction "7_7") (pintype "passive"))
      (node (ref "T62") (pin "1") (pinfunction "B_1") (pintype "passive"))
    )
    (net (code "87") (name "/6B3") (class "Default")
      (node (ref "RN71") (pin "8") (pinfunction "8_8") (pintype "passive"))
      (node (ref "T63") (pin "1") (pinfunction "B_1") (pintype "passive"))
    )
    (net (code "88") (name "/6B4") (class "Default")
      (node (ref "RN80") (pin "5") (pinfunction "5_5") (pintype "passive"))
      (node (ref "T64") (pin "1") (pinfunction "B_1") (pintype "passive"))
    )
    (net (code "89") (name "/6B5") (class "Default")
      (node (ref "RN80") (pin "6") (pinfunction "6_6") (pintype "passive"))
      (node (ref "T65") (pin "1") (pinfunction "B_1") (pintype "passive"))
    )
    (net (code "90") (name "/6B6") (class "Default")
      (node (ref "RN80") (pin "7") (pinfunction "7_7") (pintype "passive"))
      (node (ref "T66") (pin "1") (pinfunction "B_1") (pintype "passive"))
    )
    (net (code "91") (name "/6B7") (class "Default")
      (node (ref "RN80") (pin "8") (pinfunction "8_8") (pintype "passive"))
      (node (ref "T67") (pin "1") (pinfunction "B_1") (pintype "passive"))
    )
    (net (code "92") (name "/6B8") (class "Default")
      (node (ref "RN81") (pin "5") (pinfunction "5_5") (pintype "passive"))
      (node (ref "T68") (pin "1") (pinfunction "B_1") (pintype "passive"))
    )
    (net (code "93") (name "/6B9") (class "Default")
      (node (ref "RN81") (pin "6") (pinfunction "6_6") (pintype "passive"))
      (node (ref "T69") (pin "1") (pinfunction "B_1") (pintype "passive"))
    )
    (net (code "94") (name "/6C") (class "Default")
      (node (ref "IC6") (pin "2") (pinfunction "QC_2") (pintype "tri_state"))
      (node (ref "RN60") (pin "2") (pinfunction "2_2") (pintype "passive"))
    )
    (net (code "95") (name "/6D") (class "Default")
      (node (ref "IC6") (pin "3") (pinfunction "QD_3") (pintype "tri_state"))
      (node (ref "RN60") (pin "1") (pinfunction "1_1") (pintype "passive"))
    )
    (net (code "96") (name "/6E") (class "Default")
      (node (ref "IC6") (pin "4") (pinfunction "QE_4") (pintype "tri_state"))
      (node (ref "RN61") (pin "4") (pinfunction "4_4") (pintype "passive"))
    )
    (net (code "97") (name "/6F") (class "Default")
      (node (ref "IC6") (pin "5") (pinfunction "QF_5") (pintype "tri_state"))
      (node (ref "RN61") (pin "3") (pinfunction "3_3") (pintype "passive"))
    )
    (net (code "98") (name "/6G") (class "Default")
      (node (ref "IC6") (pin "6") (pinfunction "QG_6") (pintype "tri_state"))
      (node (ref "RN61") (pin "2") (pinfunction "2_2") (pintype "passive"))
    )
    (net (code "99") (name "/6H") (class "Default")
      (node (ref "IC6") (pin "7") (pinfunction "QH_7") (pintype "tri_state"))
      (node (ref "RN61") (pin "1") (pinfunction "1_1") (pintype "passive"))
    )
    (net (code "100") (name "/7A") (class "Default")
      (node (ref "IC7") (pin "15") (pinfunction "QA_15") (pintype "tri_state"))
      (node (ref "RN70") (pin "4") (pinfunction "4_4") (pintype "passive"))
    )
    (net (code "101") (name "/7B") (class "Default")
      (node (ref "IC7") (pin "1") (pinfunction "QB_1") (pintype "tri_state"))
      (node (ref "RN70") (pin "3") (pinfunction "3_3") (pintype "passive"))
    )
    (net (code "102") (name "/7C") (class "Default")
      (node (ref "IC7") (pin "2") (pinfunction "QC_2") (pintype "tri_state"))
      (node (ref "RN70") (pin "2") (pinfunction "2_2") (pintype "passive"))
    )
    (net (code "103") (name "/7D") (class "Default")
      (node (ref "IC7") (pin "3") (pinfunction "QD_3") (pintype "tri_state"))
      (node (ref "RN70") (pin "1") (pinfunction "1_1") (pintype "passive"))
    )
    (net (code "104") (name "/7E") (class "Default")
      (node (ref "IC7") (pin "4") (pinfunction "QE_4") (pintype "tri_state"))
      (node (ref "RN71") (pin "4") (pinfunction "4_4") (pintype "passive"))
    )
    (net (code "105") (name "/7F") (class "Default")
      (node (ref "IC7") (pin "5") (pinfunction "QF_5") (pintype "tri_state"))
      (node (ref "RN71") (pin "3") (pinfunction "3_3") (pintype "passive"))
    )
    (net (code "106") (name "/7G") (class "Default")
      (node (ref "IC7") (pin "6") (pinfunction "QG_6") (pintype "tri_state"))
      (node (ref "RN71") (pin "2") (pinfunction "2_2") (pintype "passive"))
    )
    (net (code "107") (name "/7H") (class "Default")
      (node (ref "IC7") (pin "7") (pinfunction "QH_7") (pintype "tri_state"))
      (node (ref "RN71") (pin "1") (pinfunction "1_1") (pintype "passive"))
    )
    (net (code "108") (name "/8A") (class "Default")
      (node (ref "IC8") (pin "15") (pinfunction "QA_15") (pintype "tri_state"))
      (node (ref "RN80") (pin "4") (pinfunction "4_4") (pintype "passive"))
    )
    (net (code "109") (name "/8B") (class "Default")
      (node (ref "IC8") (pin "1") (pinfunction "QB_1") (pintype "tri_state"))
      (node (ref "RN80") (pin "3") (pinfunction "3_3") (pintype "passive"))
    )
    (net (code "110") (name "/8C") (class "Default")
      (node (ref "IC8") (pin "2") (pinfunction "QC_2") (pintype "tri_state"))
      (node (ref "RN80") (pin "2") (pinfunction "2_2") (pintype "passive"))
    )
    (net (code "111") (name "/8D") (class "Default")
      (node (ref "IC8") (pin "3") (pinfunction "QD_3") (pintype "tri_state"))
      (node (ref "RN80") (pin "1") (pinfunction "1_1") (pintype "passive"))
    )
    (net (code "112") (name "/8E") (class "Default")
      (node (ref "IC8") (pin "4") (pinfunction "QE_4") (pintype "tri_state"))
      (node (ref "RN81") (pin "4") (pinfunction "4_4") (pintype "passive"))
    )
    (net (code "113") (name "/8F") (class "Default")
      (node (ref "IC8") (pin "5") (pinfunction "QF_5") (pintype "tri_state"))
      (node (ref "RN81") (pin "3") (pinfunction "3_3") (pintype "passive"))
    )
    (net (code "114") (name "/8G") (class "Default")
      (node (ref "IC8") (pin "6") (pinfunction "QG_6") (pintype "tri_state"))
      (node (ref "RN81") (pin "2") (pinfunction "2_2") (pintype "passive"))
    )
    (net (code "115") (name "/8H") (class "Default")
      (node (ref "IC8") (pin "7") (pinfunction "QH_7") (pintype "tri_state"))
      (node (ref "RN81") (pin "1") (pinfunction "1_1") (pintype "passive"))
    )
    (net (code "116") (name "/EN") (class "Default")
      (node (ref "IC1") (pin "13") (pinfunction "G_13") (pintype "input"))
      (node (ref "IC2") (pin "13") (pinfunction "G_13") (pintype "input"))
      (node (ref "IC3") (pin "13") (pinfunction "G_13") (pintype "input"))
      (node (ref "IC4") (pin "13") (pinfunction "G_13") (pintype "input"))
      (node (ref "IC5") (pin "13") (pinfunction "G_13") (pintype "input"))
      (node (ref "IC6") (pin "13") (pinfunction "G_13") (pintype "input"))
      (node (ref "IC7") (pin "13") (pinfunction "G_13") (pintype "input"))
      (node (ref "IC8") (pin "13") (pinfunction "G_13") (pintype "input"))
      (node (ref "JP1") (pin "1") (pinfunction "1_1") (pintype "passive"))
    )
    (net (code "117") (name "/GL1") (class "Default")
      (node (ref "RN31") (pin "5") (pinfunction "5_5") (pintype "passive"))
      (node (ref "T1") (pin "1") (pinfunction "B_1") (pintype "passive"))
    )
    (net (code "118") (name "/GL2") (class "Default")
      (node (ref "RN31") (pin "6") (pinfunction "6_6") (pintype "passive"))
      (node (ref "T2") (pin "1") (pinfunction "B_1") (pintype "passive"))
    )
    (net (code "119") (name "/GL3") (class "Default")
      (node (ref "RN60") (pin "7") (pinfunction "7_7") (pintype "passive"))
      (node (ref "T3") (pin "1") (pinfunction "B_1") (pintype "passive"))
    )
    (net (code "120") (name "/GL4") (class "Default")
      (node (ref "RN60") (pin "8") (pinfunction "8_8") (pintype "passive"))
      (node (ref "T4") (pin "1") (pinfunction "B_1") (pintype "passive"))
    )
    (net (code "121") (name "/MOSI") (class "Default")
      (node (ref "IC1") (pin "14") (pinfunction "SER_14") (pintype "input"))
      (node (ref "JP1") (pin "4") (pinfunction "4_4") (pintype "passive"))
    )
    (net (code "122") (name "/N1_B0") (class "Default")
      (node (ref "RN20") (pin "6") (pinfunction "6_6") (pintype "passive"))
      (node (ref "T11") (pin "1") (pinfunction "B_1") (pintype "passive"))
    )
    (net (code "123") (name "/N1_B1") (class "Default")
      (node (ref "RN10") (pin "5") (pinfunction "5_5") (pintype "passive"))
      (node (ref "T12") (pin "1") (pinfunction "B_1") (pintype "passive"))
    )
    (net (code "124") (name "/N1_B2") (class "Default")
      (node (ref "RN10") (pin "6") (pinfunction "6_6") (pintype "passive"))
      (node (ref "T13") (pin "1") (pinfunction "B_1") (pintype "passive"))
    )
    (net (code "125") (name "/N1_B3") (class "Default")
      (node (ref "RN10") (pin "7") (pinfunction "7_7") (pintype "passive"))
      (node (ref "T14") (pin "1") (pinfunction "B_1") (pintype "passive"))
    )
    (net (code "126") (name "/N1_B4") (class "Default")
      (node (ref "RN10") (pin "8") (pinfunction "8_8") (pintype "passive"))
      (node (ref "T15") (pin "1") (pinfunction "B_1") (pintype "passive"))
    )
    (net (code "127") (name "/N1_B5") (class "Default")
      (node (ref "RN11") (pin "5") (pinfunction "5_5") (pintype "passive"))
      (node (ref "T16") (pin "1") (pinfunction "B_1") (pintype "passive"))
    )
    (net (code "128") (name "/N1_B6") (class "Default")
      (node (ref "RN11") (pin "6") (pinfunction "6_6") (pintype "passive"))
      (node (ref "T17") (pin "1") (pinfunction "B_1") (pintype "passive"))
    )
    (net (code "129") (name "/N1_B7") (class "Default")
      (node (ref "RN11") (pin "7") (pinfunction "7_7") (pintype "passive"))
      (node (ref "T18") (pin "1") (pinfunction "B_1") (pintype "passive"))
    )
    (net (code "130") (name "/N1_B8") (class "Default")
      (node (ref "RN11") (pin "8") (pinfunction "8_8") (pintype "passive"))
      (node (ref "T19") (pin "1") (pinfunction "B_1") (pintype "passive"))
    )
    (net (code "131") (name "/N1_B9") (class "Default")
      (node (ref "RN20") (pin "5") (pinfunction "5_5") (pintype "passive"))
      (node (ref "T10") (pin "1") (pinfunction "B_1") (pintype "passive"))
    )
    (net (code "132") (name "/N1_K0") (class "Default")
      (node (ref "T12") (pin "3") (pinfunction "C_3") (pintype "passive"))
      (node (ref "U$4") (pin "P10") (pinfunction "0_P10") (pintype "bidirectional"))
    )
    (net (code "133") (name "/N1_K1") (class "Default")
      (node (ref "T11") (pin "3") (pinfunction "C_3") (pintype "passive"))
      (node (ref "U$4") (pin "P1") (pinfunction "1_P1") (pintype "bidirectional"))
    )
    (net (code "134") (name "/N1_K2") (class "Default")
      (node (ref "T10") (pin "3") (pinfunction "C_3") (pintype "passive"))
      (node (ref "U$4") (pin "P2") (pinfunction "2_P2") (pintype "bidirectional"))
    )
    (net (code "135") (name "/N1_K3") (class "Default")
      (node (ref "T19") (pin "3") (pinfunction "C_3") (pintype "passive"))
      (node (ref "U$4") (pin "P3") (pinfunction "3_P3") (pintype "bidirectional"))
    )
    (net (code "136") (name "/N1_K4") (class "Default")
      (node (ref "T18") (pin "3") (pinfunction "C_3") (pintype "passive"))
      (node (ref "U$4") (pin "P4") (pinfunction "4_P4") (pintype "bidirectional"))
    )
    (net (code "137") (name "/N1_K5") (class "Default")
      (node (ref "T17") (pin "3") (pinfunction "C_3") (pintype "passive"))
      (node (ref "U$4") (pin "P5") (pinfunction "5_P5") (pintype "bidirectional"))
    )
    (net (code "138") (name "/N1_K6") (class "Default")
      (node (ref "T16") (pin "3") (pinfunction "C_3") (pintype "passive"))
      (node (ref "U$4") (pin "P6") (pinfunction "6_P6") (pintype "bidirectional"))
    )
    (net (code "139") (name "/N1_K7") (class "Default")
      (node (ref "T15") (pin "3") (pinfunction "C_3") (pintype "passive"))
      (node (ref "U$4") (pin "P7") (pinfunction "7_P7") (pintype "bidirectional"))
    )
    (net (code "140") (name "/N1_K8") (class "Default")
      (node (ref "T14") (pin "3") (pinfunction "C_3") (pintype "passive"))
      (node (ref "U$4") (pin "P8") (pinfunction "8_P8") (pintype "bidirectional"))
    )
    (net (code "141") (name "/N1_K9") (class "Default")
      (node (ref "T13") (pin "3") (pinfunction "C_3") (pintype "passive"))
      (node (ref "U$4") (pin "P9") (pinfunction "9_P9") (pintype "bidirectional"))
    )
    (net (code "142") (name "/N2_0") (class "Default")
      (node (ref "T22") (pin "3") (pinfunction "C_3") (pintype "passive"))
      (node (ref "U$5") (pin "P10") (pinfunction "0_P10") (pintype "bidirectional"))
    )
    (net (code "143") (name "/N2_1") (class "Default")
      (node (ref "T21") (pin "3") (pinfunction "C_3") (pintype "passive"))
      (node (ref "U$5") (pin "P1") (pinfunction "1_P1") (pintype "bidirectional"))
    )
    (net (code "144") (name "/N2_2") (class "Default")
      (node (ref "T20") (pin "3") (pinfunction "C_3") (pintype "passive"))
      (node (ref "U$5") (pin "P2") (pinfunction "2_P2") (pintype "bidirectional"))
    )
    (net (code "145") (name "/N2_3") (class "Default")
      (node (ref "T29") (pin "3") (pinfunction "C_3") (pintype "passive"))
      (node (ref "U$5") (pin "P3") (pinfunction "3_P3") (pintype "bidirectional"))
    )
    (net (code "146") (name "/N2_4") (class "Default")
      (node (ref "T28") (pin "3") (pinfunction "C_3") (pintype "passive"))
      (node (ref "U$5") (pin "P4") (pinfunction "4_P4") (pintype "bidirectional"))
    )
    (net (code "147") (name "/N2_5") (class "Default")
      (node (ref "T27") (pin "3") (pinfunction "C_3") (pintype "passive"))
      (node (ref "U$5") (pin "P5") (pinfunction "5_P5") (pintype "bidirectional"))
    )
    (net (code "148") (name "/N2_6") (class "Default")
      (node (ref "T26") (pin "3") (pinfunction "C_3") (pintype "passive"))
      (node (ref "U$5") (pin "P6") (pinfunction "6_P6") (pintype "bidirectional"))
    )
    (net (code "149") (name "/N2_7") (class "Default")
      (node (ref "T25") (pin "3") (pinfunction "C_3") (pintype "passive"))
      (node (ref "U$5") (pin "P7") (pinfunction "7_P7") (pintype "bidirectional"))
    )
    (net (code "150") (name "/N2_8") (class "Default")
      (node (ref "T24") (pin "3") (pinfunction "C_3") (pintype "passive"))
      (node (ref "U$5") (pin "P8") (pinfunction "8_P8") (pintype "bidirectional"))
    )
    (net (code "151") (name "/N2_9") (class "Default")
      (node (ref "T23") (pin "3") (pinfunction "C_3") (pintype "passive"))
      (node (ref "U$5") (pin "P9") (pinfunction "9_P9") (pintype "bidirectional"))
    )
    (net (code "152") (name "/N3_0") (class "Default")
      (node (ref "T32") (pin "3") (pinfunction "C_3") (pintype "passive"))
      (node (ref "U$6") (pin "P10") (pinfunction "0_P10") (pintype "bidirectional"))
    )
    (net (code "153") (name "/N3_1") (class "Default")
      (node (ref "T31") (pin "3") (pinfunction "C_3") (pintype "passive"))
      (node (ref "U$6") (pin "P1") (pinfunction "1_P1") (pintype "bidirectional"))
    )
    (net (code "154") (name "/N3_2") (class "Default")
      (node (ref "T30") (pin "3") (pinfunction "C_3") (pintype "passive"))
      (node (ref "U$6") (pin "P2") (pinfunction "2_P2") (pintype "bidirectional"))
    )
    (net (code "155") (name "/N3_3") (class "Default")
      (node (ref "T39") (pin "3") (pinfunction "C_3") (pintype "passive"))
      (node (ref "U$6") (pin "P3") (pinfunction "3_P3") (pintype "bidirectional"))
    )
    (net (code "156") (name "/N3_4") (class "Default")
      (node (ref "T38") (pin "3") (pinfunction "C_3") (pintype "passive"))
      (node (ref "U$6") (pin "P4") (pinfunction "4_P4") (pintype "bidirectional"))
    )
    (net (code "157") (name "/N3_5") (class "Default")
      (node (ref "T37") (pin "3") (pinfunction "C_3") (pintype "passive"))
      (node (ref "U$6") (pin "P5") (pinfunction "5_P5") (pintype "bidirectional"))
    )
    (net (code "158") (name "/N3_6") (class "Default")
      (node (ref "T36") (pin "3") (pinfunction "C_3") (pintype "passive"))
      (node (ref "U$6") (pin "P6") (pinfunction "6_P6") (pintype "bidirectional"))
    )
    (net (code "159") (name "/N3_7") (class "Default")
      (node (ref "T35") (pin "3") (pinfunction "C_3") (pintype "passive"))
      (node (ref "U$6") (pin "P7") (pinfunction "7_P7") (pintype "bidirectional"))
    )
    (net (code "160") (name "/N3_8") (class "Default")
      (node (ref "T34") (pin "3") (pinfunction "C_3") (pintype "passive"))
      (node (ref "U$6") (pin "P8") (pinfunction "8_P8") (pintype "bidirectional"))
    )
    (net (code "161") (name "/N3_9") (class "Default")
      (node (ref "T33") (pin "3") (pinfunction "C_3") (pintype "passive"))
      (node (ref "U$6") (pin "P9") (pinfunction "9_P9") (pintype "bidirectional"))
    )
    (net (code "162") (name "/N4_0") (class "Default")
      (node (ref "T42") (pin "3") (pinfunction "C_3") (pintype "passive"))
      (node (ref "U$7") (pin "P10") (pinfunction "0_P10") (pintype "bidirectional"))
    )
    (net (code "163") (name "/N4_1") (class "Default")
      (node (ref "T41") (pin "3") (pinfunction "C_3") (pintype "passive"))
      (node (ref "U$7") (pin "P1") (pinfunction "1_P1") (pintype "bidirectional"))
    )
    (net (code "164") (name "/N4_2") (class "Default")
      (node (ref "T40") (pin "3") (pinfunction "C_3") (pintype "passive"))
      (node (ref "U$7") (pin "P2") (pinfunction "2_P2") (pintype "bidirectional"))
    )
    (net (code "165") (name "/N4_3") (class "Default")
      (node (ref "T49") (pin "3") (pinfunction "C_3") (pintype "passive"))
      (node (ref "U$7") (pin "P3") (pinfunction "3_P3") (pintype "bidirectional"))
    )
    (net (code "166") (name "/N4_4") (class "Default")
      (node (ref "T48") (pin "3") (pinfunction "C_3") (pintype "passive"))
      (node (ref "U$7") (pin "P4") (pinfunction "4_P4") (pintype "bidirectional"))
    )
    (net (code "167") (name "/N4_5") (class "Default")
      (node (ref "T47") (pin "3") (pinfunction "C_3") (pintype "passive"))
      (node (ref "U$7") (pin "P5") (pinfunction "5_P5") (pintype "bidirectional"))
    )
    (net (code "168") (name "/N4_6") (class "Default")
      (node (ref "T46") (pin "3") (pinfunction "C_3") (pintype "passive"))
      (node (ref "U$7") (pin "P6") (pinfunction "6_P6") (pintype "bidirectional"))
    )
    (net (code "169") (name "/N4_7") (class "Default")
      (node (ref "T45") (pin "3") (pinfunction "C_3") (pintype "passive"))
      (node (ref "U$7") (pin "P7") (pinfunction "7_P7") (pintype "bidirectional"))
    )
    (net (code "170") (name "/N4_8") (class "Default")
      (node (ref "T44") (pin "3") (pinfunction "C_3") (pintype "passive"))
      (node (ref "U$7") (pin "P8") (pinfunction "8_P8") (pintype "bidirectional"))
    )
    (net (code "171") (name "/N4_9") (class "Default")
      (node (ref "T43") (pin "3") (pinfunction "C_3") (pintype "passive"))
      (node (ref "U$7") (pin "P9") (pinfunction "9_P9") (pintype "bidirectional"))
    )
    (net (code "172") (name "/N5_0") (class "Default")
      (node (ref "T52") (pin "3") (pinfunction "C_3") (pintype "passive"))
      (node (ref "U$8") (pin "P10") (pinfunction "0_P10") (pintype "bidirectional"))
    )
    (net (code "173") (name "/N5_1") (class "Default")
      (node (ref "T51") (pin "3") (pinfunction "C_3") (pintype "passive"))
      (node (ref "U$8") (pin "P1") (pinfunction "1_P1") (pintype "bidirectional"))
    )
    (net (code "174") (name "/N5_2") (class "Default")
      (node (ref "T50") (pin "3") (pinfunction "C_3") (pintype "passive"))
      (node (ref "U$8") (pin "P2") (pinfunction "2_P2") (pintype "bidirectional"))
    )
    (net (code "175") (name "/N5_3") (class "Default")
      (node (ref "T59") (pin "3") (pinfunction "C_3") (pintype "passive"))
      (node (ref "U$8") (pin "P3") (pinfunction "3_P3") (pintype "bidirectional"))
    )
    (net (code "176") (name "/N5_4") (class "Default")
      (node (ref "T58") (pin "3") (pinfunction "C_3") (pintype "passive"))
      (node (ref "U$8") (pin "P4") (pinfunction "4_P4") (pintype "bidirectional"))
    )
    (net (code "177") (name "/N5_5") (class "Default")
      (node (ref "T57") (pin "3") (pinfunction "C_3") (pintype "passive"))
      (node (ref "U$8") (pin "P5") (pinfunction "5_P5") (pintype "bidirectional"))
    )
    (net (code "178") (name "/N5_6") (class "Default")
      (node (ref "T56") (pin "3") (pinfunction "C_3") (pintype "passive"))
      (node (ref "U$8") (pin "P6") (pinfunction "6_P6") (pintype "bidirectional"))
    )
    (net (code "179") (name "/N5_7") (class "Default")
      (node (ref "T55") (pin "3") (pinfunction "C_3") (pintype "passive"))
      (node (ref "U$8") (pin "P7") (pinfunction "7_P7") (pintype "bidirectional"))
    )
    (net (code "180") (name "/N5_8") (class "Default")
      (node (ref "T54") (pin "3") (pinfunction "C_3") (pintype "passive"))
      (node (ref "U$8") (pin "P8") (pinfunction "8_P8") (pintype "bidirectional"))
    )
    (net (code "181") (name "/N5_9") (class "Default")
      (node (ref "T53") (pin "3") (pinfunction "C_3") (pintype "passive"))
      (node (ref "U$8") (pin "P9") (pinfunction "9_P9") (pintype "bidirectional"))
    )
    (net (code "182") (name "/N6_0") (class "Default")
      (node (ref "T62") (pin "3") (pinfunction "C_3") (pintype "passive"))
      (node (ref "U$9") (pin "P10") (pinfunction "0_P10") (pintype "bidirectional"))
    )
    (net (code "183") (name "/N6_1") (class "Default")
      (node (ref "T61") (pin "3") (pinfunction "C_3") (pintype "passive"))
      (node (ref "U$9") (pin "P1") (pinfunction "1_P1") (pintype "bidirectional"))
    )
    (net (code "184") (name "/N6_2") (class "Default")
      (node (ref "T60") (pin "3") (pinfunction "C_3") (pintype "passive"))
      (node (ref "U$9") (pin "P2") (pinfunction "2_P2") (pintype "bidirectional"))
    )
    (net (code "185") (name "/N6_3") (class "Default")
      (node (ref "T69") (pin "3") (pinfunction "C_3") (pintype "passive"))
      (node (ref "U$9") (pin "P3") (pinfunction "3_P3") (pintype "bidirectional"))
    )
    (net (code "186") (name "/N6_4") (class "Default")
      (node (ref "T68") (pin "3") (pinfunction "C_3") (pintype "passive"))
      (node (ref "U$9") (pin "P4") (pinfunction "4_P4") (pintype "bidirectional"))
    )
    (net (code "187") (name "/N6_5") (class "Default")
      (node (ref "T67") (pin "3") (pinfunction "C_3") (pintype "passive"))
      (node (ref "U$9") (pin "P5") (pinfunction "5_P5") (pintype "bidirectional"))
    )
    (net (code "188") (name "/N6_6") (class "Default")
      (node (ref "T66") (pin "3") (pinfunction "C_3") (pintype "passive"))
      (node (ref "U$9") (pin "P6") (pinfunction "6_P6") (pintype "bidirectional"))
    )
    (net (code "189") (name "/N6_7") (class "Default")
      (node (ref "T65") (pin "3") (pinfunction "C_3") (pintype "passive"))
      (node (ref "U$9") (pin "P7") (pinfunction "7_P7") (pintype "bidirectional"))
    )
    (net (code "190") (name "/N6_8") (class "Default")
      (node (ref "T64") (pin "3") (pinfunction "C_3") (pintype "passive"))
      (node (ref "U$9") (pin "P8") (pinfunction "8_P8") (pintype "bidirectional"))
    )
    (net (code "191") (name "/N6_9") (class "Default")
      (node (ref "T63") (pin "3") (pinfunction "C_3") (pintype "passive"))
      (node (ref "U$9") (pin "P9") (pinfunction "9_P9") (pintype "bidirectional"))
    )
    (net (code "192") (name "/RCK") (class "Default")
      (node (ref "IC1") (pin "12") (pinfunction "RCK_12") (pintype "input"))
      (node (ref "IC2") (pin "12") (pinfunction "RCK_12") (pintype "input"))
      (node (ref "IC3") (pin "12") (pinfunction "RCK_12") (pintype "input"))
      (node (ref "IC4") (pin "12") (pinfunction "RCK_12") (pintype "input"))
      (node (ref "IC5") (pin "12") (pinfunction "RCK_12") (pintype "input"))
      (node (ref "IC6") (pin "12") (pinfunction "RCK_12") (pintype "input"))
      (node (ref "IC7") (pin "12") (pinfunction "RCK_12") (pintype "input"))
      (node (ref "IC8") (pin "12") (pinfunction "RCK_12") (pintype "input"))
      (node (ref "JP1") (pin "5") (pinfunction "5_5") (pintype "passive"))
    )
    (net (code "193") (name "/SCK") (class "Default")
      (node (ref "IC1") (pin "11") (pinfunction "SCK_11") (pintype "input"))
      (node (ref "IC2") (pin "11") (pinfunction "SCK_11") (pintype "input"))
      (node (ref "IC3") (pin "11") (pinfunction "SCK_11") (pintype "input"))
      (node (ref "IC4") (pin "11") (pinfunction "SCK_11") (pintype "input"))
      (node (ref "IC5") (pin "11") (pinfunction "SCK_11") (pintype "input"))
      (node (ref "IC6") (pin "11") (pinfunction "SCK_11") (pintype "input"))
      (node (ref "IC7") (pin "11") (pinfunction "SCK_11") (pintype "input"))
      (node (ref "IC8") (pin "11") (pinfunction "SCK_11") (pintype "input"))
      (node (ref "JP1") (pin "3") (pinfunction "3_3") (pintype "passive"))
    )
    (net (code "194") (name "/SCL") (class "Default")
      (node (ref "IC1") (pin "10") (pinfunction "SCL_10") (pintype "input"))
      (node (ref "IC2") (pin "10") (pinfunction "SCL_10") (pintype "input"))
      (node (ref "IC3") (pin "10") (pinfunction "SCL_10") (pintype "input"))
      (node (ref "IC4") (pin "10") (pinfunction "SCL_10") (pintype "input"))
      (node (ref "IC5") (pin "10") (pinfunction "SCL_10") (pintype "input"))
      (node (ref "IC6") (pin "10") (pinfunction "SCL_10") (pintype "input"))
      (node (ref "IC7") (pin "10") (pinfunction "SCL_10") (pintype "input"))
      (node (ref "IC8") (pin "10") (pinfunction "SCL_10") (pintype "input"))
      (node (ref "JP1") (pin "2") (pinfunction "2_2") (pintype "passive"))
    )
    (net (code "195") (name "GND") (class "Default")
      (node (ref "C1") (pin "2") (pinfunction "2_2") (pintype "passive"))
      (node (ref "C2") (pin "2") (pinfunction "2_2") (pintype "passive"))
      (node (ref "C3") (pin "2") (pinfunction "2_2") (pintype "passive"))
      (node (ref "C4") (pin "2") (pinfunction "2_2") (pintype "passive"))
      (node (ref "C5") (pin "2") (pinfunction "2_2") (pintype "passive"))
      (node (ref "C6") (pin "2") (pinfunction "2_2") (pintype "passive"))
      (node (ref "C7") (pin "2") (pinfunction "2_2") (pintype "passive"))
      (node (ref "C8") (pin "2") (pinfunction "2_2") (pintype "passive"))
      (node (ref "IC1") (pin "8") (pinfunction "GND_8") (pintype "power_in"))
      (node (ref "IC2") (pin "8") (pinfunction "GND_8") (pintype "power_in"))
      (node (ref "IC3") (pin "8") (pinfunction "GND_8") (pintype "power_in"))
      (node (ref "IC4") (pin "8") (pinfunction "GND_8") (pintype "power_in"))
      (node (ref "IC5") (pin "8") (pinfunction "GND_8") (pintype "power_in"))
      (node (ref "IC6") (pin "8") (pinfunction "GND_8") (pintype "power_in"))
      (node (ref "IC7") (pin "8") (pinfunction "GND_8") (pintype "power_in"))
      (node (ref "IC8") (pin "8") (pinfunction "GND_8") (pintype "power_in"))
      (node (ref "JP1") (pin "6") (pinfunction "6_6") (pintype "passive"))
      (node (ref "JP2") (pin "2") (pinfunction "2_2") (pintype "passive"))
      (node (ref "JP2") (pin "3") (pinfunction "3_3") (pintype "passive"))
      (node (ref "JP2") (pin "4") (pinfunction "4_4") (pintype "passive"))
      (node (ref "JP2") (pin "5") (pinfunction "5_5") (pintype "passive"))
      (node (ref "T1") (pin "2") (pinfunction "E_2") (pintype "passive"))
      (node (ref "T10") (pin "2") (pinfunction "E_2") (pintype "passive"))
      (node (ref "T11") (pin "2") (pinfunction "E_2") (pintype "passive"))
      (node (ref "T12") (pin "2") (pinfunction "E_2") (pintype "passive"))
      (node (ref "T13") (pin "2") (pinfunction "E_2") (pintype "passive"))
      (node (ref "T14") (pin "2") (pinfunction "E_2") (pintype "passive"))
      (node (ref "T15") (pin "2") (pinfunction "E_2") (pintype "passive"))
      (node (ref "T16") (pin "2") (pinfunction "E_2") (pintype "passive"))
      (node (ref "T17") (pin "2") (pinfunction "E_2") (pintype "passive"))
      (node (ref "T18") (pin "2") (pinfunction "E_2") (pintype "passive"))
      (node (ref "T19") (pin "2") (pinfunction "E_2") (pintype "passive"))
      (node (ref "T2") (pin "2") (pinfunction "E_2") (pintype "passive"))
      (node (ref "T20") (pin "2") (pinfunction "E_2") (pintype "passive"))
      (node (ref "T21") (pin "2") (pinfunction "E_2") (pintype "passive"))
      (node (ref "T22") (pin "2") (pinfunction "E_2") (pintype "passive"))
      (node (ref "T23") (pin "2") (pinfunction "E_2") (pintype "passive"))
      (node (ref "T24") (pin "2") (pinfunction "E_2") (pintype "passive"))
      (node (ref "T25") (pin "2") (pinfunction "E_2") (pintype "passive"))
      (node (ref "T26") (pin "2") (pinfunction "E_2") (pintype "passive"))
      (node (ref "T27") (pin "2") (pinfunction "E_2") (pintype "passive"))
      (node (ref "T28") (pin "2") (pinfunction "E_2") (pintype "passive"))
      (node (ref "T29") (pin "2") (pinfunction "E_2") (pintype "passive"))
      (node (ref "T3") (pin "2") (pinfunction "E_2") (pintype "passive"))
      (node (ref "T30") (pin "2") (pinfunction "E_2") (pintype "passive"))
      (node (ref "T31") (pin "2") (pinfunction "E_2") (pintype "passive"))
      (node (ref "T32") (pin "2") (pinfunction "E_2") (pintype "passive"))
      (node (ref "T33") (pin "2") (pinfunction "E_2") (pintype "passive"))
      (node (ref "T34") (pin "2") (pinfunction "E_2") (pintype "passive"))
      (node (ref "T35") (pin "2") (pinfunction "E_2") (pintype "passive"))
      (node (ref "T36") (pin "2") (pinfunction "E_2") (pintype "passive"))
      (node (ref "T37") (pin "2") (pinfunction "E_2") (pintype "passive"))
      (node (ref "T38") (pin "2") (pinfunction "E_2") (pintype "passive"))
      (node (ref "T39") (pin "2") (pinfunction "E_2") (pintype "passive"))
      (node (ref "T4") (pin "2") (pinfunction "E_2") (pintype "passive"))
      (node (ref "T40") (pin "2") (pinfunction "E_2") (pintype "passive"))
      (node (ref "T41") (pin "2") (pinfunction "E_2") (pintype "passive"))
      (node (ref "T42") (pin "2") (pinfunction "E_2") (pintype "passive"))
      (node (ref "T43") (pin "2") (pinfunction "E_2") (pintype "passive"))
      (node (ref "T44") (pin "2") (pinfunction "E_2") (pintype "passive"))
      (node (ref "T45") (pin "2") (pinfunction "E_2") (pintype "passive"))
      (node (ref "T46") (pin "2") (pinfunction "E_2") (pintype "passive"))
      (node (ref "T47") (pin "2") (pinfunction "E_2") (pintype "passive"))
      (node (ref "T48") (pin "2") (pinfunction "E_2") (pintype "passive"))
      (node (ref "T49") (pin "2") (pinfunction "E_2") (pintype "passive"))
      (node (ref "T50") (pin "2") (pinfunction "E_2") (pintype "passive"))
      (node (ref "T51") (pin "2") (pinfunction "E_2") (pintype "passive"))
      (node (ref "T52") (pin "2") (pinfunction "E_2") (pintype "passive"))
      (node (ref "T53") (pin "2") (pinfunction "E_2") (pintype "passive"))
      (node (ref "T54") (pin "2") (pinfunction "E_2") (pintype "passive"))
      (node (ref "T55") (pin "2") (pinfunction "E_2") (pintype "passive"))
      (node (ref "T56") (pin "2") (pinfunction "E_2") (pintype "passive"))
      (node (ref "T57") (pin "2") (pinfunction "E_2") (pintype "passive"))
      (node (ref "T58") (pin "2") (pinfunction "E_2") (pintype "passive"))
      (node (ref "T59") (pin "2") (pinfunction "E_2") (pintype "passive"))
      (node (ref "T60") (pin "2") (pinfunction "E_2") (pintype "passive"))
      (node (ref "T61") (pin "2") (pinfunction "E_2") (pintype "passive"))
      (node (ref "T62") (pin "2") (pinfunction "E_2") (pintype "passive"))
      (node (ref "T63") (pin "2") (pinfunction "E_2") (pintype "passive"))
      (node (ref "T64") (pin "2") (pinfunction "E_2") (pintype "passive"))
      (node (ref "T65") (pin "2") (pinfunction "E_2") (pintype "passive"))
      (node (ref "T66") (pin "2") (pinfunction "E_2") (pintype "passive"))
      (node (ref "T67") (pin "2") (pinfunction "E_2") (pintype "passive"))
      (node (ref "T68") (pin "2") (pinfunction "E_2") (pintype "passive"))
      (node (ref "T69") (pin "2") (pinfunction "E_2") (pintype "passive"))
    )
    (net (code "196") (name "Net-(GL1-A)") (class "Default")
      (node (ref "GL1") (pin "1") (pinfunction "A_1") (pintype "passive"))
      (node (ref "R1") (pin "1") (pinfunction "1_1") (pintype "passive"))
    )
    (net (code "197") (name "Net-(GL1-A1)") (class "Default")
      (node (ref "GL1") (pin "2") (pinfunction "A1_2") (pintype "passive"))
      (node (ref "T1") (pin "3") (pinfunction "C_3") (pintype "passive"))
    )
    (net (code "198") (name "Net-(GL2-A)") (class "Default")
      (node (ref "GL2") (pin "1") (pinfunction "A_1") (pintype "passive"))
      (node (ref "R2") (pin "1") (pinfunction "1_1") (pintype "passive"))
    )
    (net (code "199") (name "Net-(GL2-A1)") (class "Default")
      (node (ref "GL2") (pin "2") (pinfunction "A1_2") (pintype "passive"))
      (node (ref "T2") (pin "3") (pinfunction "C_3") (pintype "passive"))
    )
    (net (code "200") (name "Net-(GL3-A)") (class "Default")
      (node (ref "GL3") (pin "1") (pinfunction "A_1") (pintype "passive"))
      (node (ref "R3") (pin "1") (pinfunction "1_1") (pintype "passive"))
    )
    (net (code "201") (name "Net-(GL3-A1)") (class "Default")
      (node (ref "GL3") (pin "2") (pinfunction "A1_2") (pintype "passive"))
      (node (ref "T3") (pin "3") (pinfunction "C_3") (pintype "passive"))
    )
    (net (code "202") (name "Net-(GL4-A)") (class "Default")
      (node (ref "GL4") (pin "1") (pinfunction "A_1") (pintype "passive"))
      (node (ref "R4") (pin "1") (pinfunction "1_1") (pintype "passive"))
    )
    (net (code "203") (name "Net-(GL4-A1)") (class "Default")
      (node (ref "GL4") (pin "2") (pinfunction "A1_2") (pintype "passive"))
      (node (ref "T4") (pin "3") (pinfunction "C_3") (pintype "passive"))
    )
    (net (code "204") (name "Net-(IC1A-QH*)") (class "Default")
      (node (ref "IC1") (pin "9") (pinfunction "QH*_9") (pintype "tri_state"))
      (node (ref "IC2") (pin "14") (pinfunction "SER_14") (pintype "input"))
    )
    (net (code "205") (name "Net-(IC2A-QH*)") (class "Default")
      (node (ref "IC2") (pin "9") (pinfunction "QH*_9") (pintype "tri_state"))
      (node (ref "IC3") (pin "14") (pinfunction "SER_14") (pintype "input"))
    )
    (net (code "206") (name "Net-(IC3A-QH*)") (class "Default")
      (node (ref "IC3") (pin "9") (pinfunction "QH*_9") (pintype "tri_state"))
      (node (ref "IC4") (pin "14") (pinfunction "SER_14") (pintype "input"))
    )
    (net (code "207") (name "Net-(IC4A-QH*)") (class "Default")
      (node (ref "IC4") (pin "9") (pinfunction "QH*_9") (pintype "tri_state"))
      (node (ref "IC5") (pin "14") (pinfunction "SER_14") (pintype "input"))
    )
    (net (code "208") (name "Net-(IC5A-QH*)") (class "Default")
      (node (ref "IC5") (pin "9") (pinfunction "QH*_9") (pintype "tri_state"))
      (node (ref "IC6") (pin "14") (pinfunction "SER_14") (pintype "input"))
    )
    (net (code "209") (name "Net-(IC6A-QH*)") (class "Default")
      (node (ref "IC6") (pin "9") (pinfunction "QH*_9") (pintype "tri_state"))
      (node (ref "IC7") (pin "14") (pinfunction "SER_14") (pintype "input"))
    )
    (net (code "210") (name "Net-(IC7A-QH*)") (class "Default")
      (node (ref "IC7") (pin "9") (pinfunction "QH*_9") (pintype "tri_state"))
      (node (ref "IC8") (pin "14") (pinfunction "SER_14") (pintype "input"))
    )
    (net (code "211") (name "Net-(U$4-A)") (class "Default")
      (node (ref "R10") (pin "1") (pinfunction "1_1") (pintype "passive"))
      (node (ref "U$4") (pin "P11") (pinfunction "A_P11") (pintype "bidirectional"))
    )
    (net (code "212") (name "Net-(U$5-A)") (class "Default")
      (node (ref "R20") (pin "1") (pinfunction "1_1") (pintype "passive"))
      (node (ref "U$5") (pin "P11") (pinfunction "A_P11") (pintype "bidirectional"))
    )
    (net (code "213") (name "Net-(U$6-A)") (class "Default")
      (node (ref "R30") (pin "1") (pinfunction "1_1") (pintype "passive"))
      (node (ref "U$6") (pin "P11") (pinfunction "A_P11") (pintype "bidirectional"))
    )
    (net (code "214") (name "Net-(U$7-A)") (class "Default")
      (node (ref "R40") (pin "1") (pinfunction "1_1") (pintype "passive"))
      (node (ref "U$7") (pin "P11") (pinfunction "A_P11") (pintype "bidirectional"))
    )
    (net (code "215") (name "Net-(U$8-A)") (class "Default")
      (node (ref "R50") (pin "1") (pinfunction "1_1") (pintype "passive"))
      (node (ref "U$8") (pin "P11") (pinfunction "A_P11") (pintype "bidirectional"))
    )
    (net (code "216") (name "Net-(U$9-A)") (class "Default")
      (node (ref "R60") (pin "1") (pinfunction "1_1") (pintype "passive"))
      (node (ref "U$9") (pin "P11") (pinfunction "A_P11") (pintype "bidirectional"))
    )
    (net (code "217") (name "VDD") (class "Default")
      (node (ref "JP2") (pin "1") (pinfunction "1_1") (pintype "passive"))
      (node (ref "R1") (pin "2") (pinfunction "2_2") (pintype "passive"))
      (node (ref "R10") (pin "2") (pinfunction "2_2") (pintype "passive"))
      (node (ref "R2") (pin "2") (pinfunction "2_2") (pintype "passive"))
      (node (ref "R20") (pin "2") (pinfunction "2_2") (pintype "passive"))
      (node (ref "R3") (pin "2") (pinfunction "2_2") (pintype "passive"))
      (node (ref "R30") (pin "2") (pinfunction "2_2") (pintype "passive"))
      (node (ref "R4") (pin "2") (pinfunction "2_2") (pintype "passive"))
      (node (ref "R40") (pin "2") (pinfunction "2_2") (pintype "passive"))
      (node (ref "R50") (pin "2") (pinfunction "2_2") (pintype "passive"))
      (node (ref "R60") (pin "2") (pinfunction "2_2") (pintype "passive"))
    )
    (net (code "218") (name "unconnected-(IC8A-QH*-Pad9)") (class "Default")
      (node (ref "IC8") (pin "9") (pinfunction "QH*_9") (pintype "tri_state"))
    )
  )
)
